# AdaptiveLightingHub.net
KiCad netlist of a schematic drawn in Altium Designer
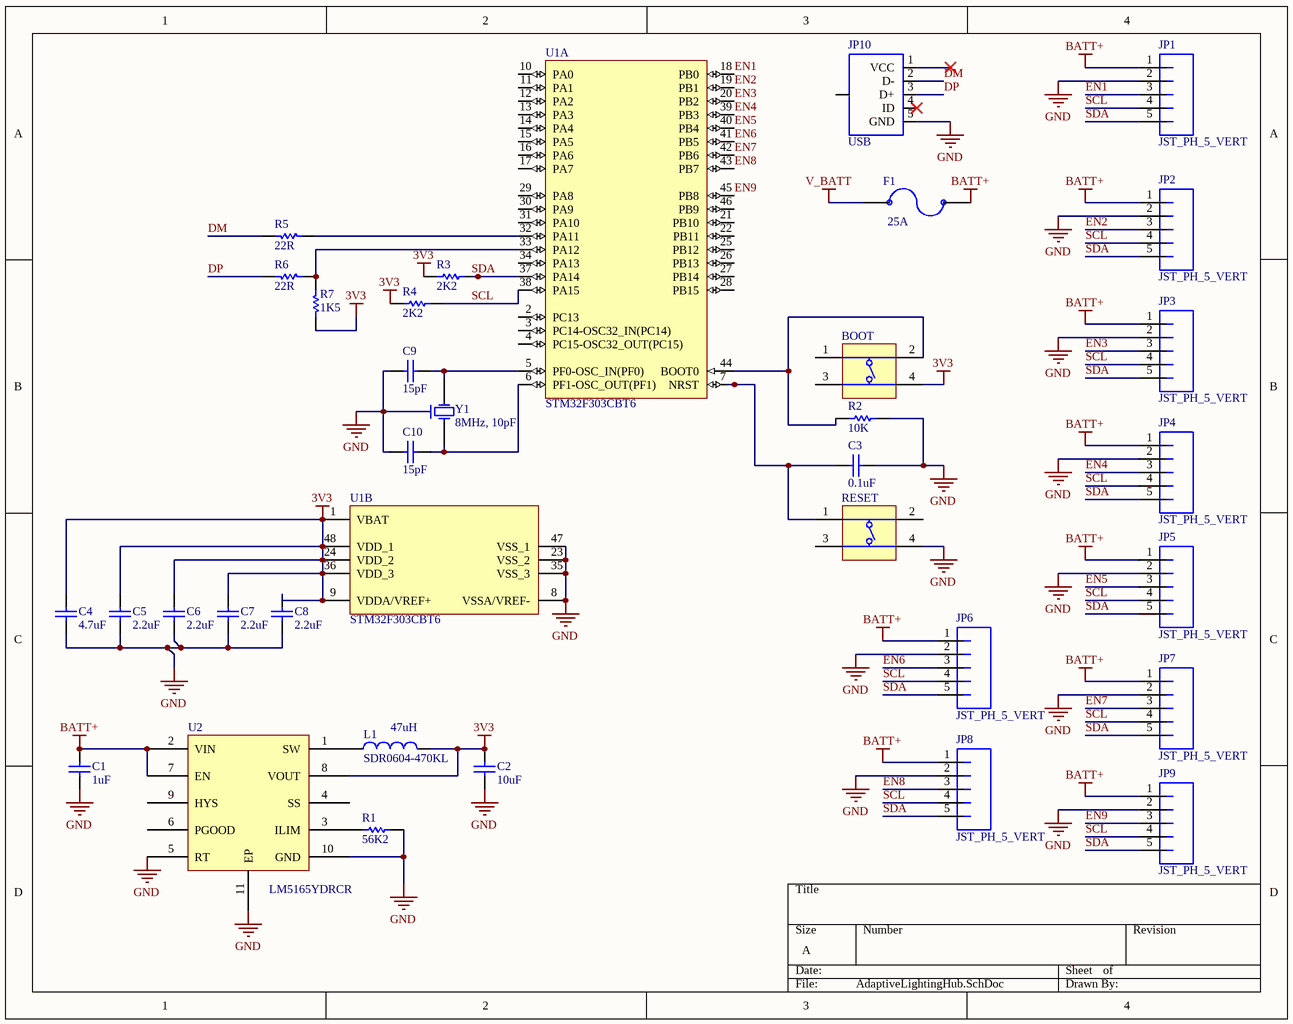
[diagram p0: AdaptiveLightingHub.SchDoc]

(export (version "E")
  (design (tool "Eeschema 10.0.6"))
  (components
    (comp (ref "BOOT")
      (value "~")
      (footprint "SWITCH")
      (description "Switch, SPNO Push Button SMD")
      (fields
        (field (name "MANUFACTURER") "C&K Components")
        (field (name "PARTNUMBER") "PTS810 SJM 250 SMTR LFS")
      )
      (libsource (lib "Components") (part "DIPT-DTSM-6"))
    )
    (comp (ref "C1")
      (value "1uF")
      (footprint "C0805[2012X120]")
      (description "CAP_1uF 100V 20% 0805 (2012 metric)")
      (fields (field (name "MANUFACTURER") "TDK") (field (name "PARTNUMBER") "C2012X7S2A474M125AE"))
      (libsource (lib "Capacitors") (part "CAP_1uF_100V_0805_20%"))
    )
    (comp (ref "C2")
      (value "10uF")
      (footprint "C0402[1005X55]")
      (description "10uF 6.3V 20% 0402 (1005 Metric)")
      (fields (field (name "PARTNUMBER") "GRM155R60J106ME44D") (field (name "MANUFACTURER") "Murata"))
      (libsource (lib "Capacitors") (part "CAP_10uF_6.3V_0402_20%"))
    )
    (comp (ref "C3")
      (value "0.1uF")
      (footprint "C0402[1005X55]")
      (description "0.1uF 6.3V 10% 0402 (1005 Metric)")
      (fields (field (name "TOLERANCE") "10%") (field (name "PARTNUMBER") "GRM155R70J104KA01D"))
      (libsource (lib "Capacitors") (part "CAP_0.1uF_6.3V_0402_10%"))
    )
    (comp (ref "C4")
      (value "4.7uF")
      (footprint "C0402[1005X55]")
      (description "4.7uF 6.3V 20% 0402 (1005 Metric)")
      (fields (field (name "TOLERANCE") "20%") (field (name "PARTNUMBER") "GRM155R60J475ME47D"))
      (libsource (lib "Capacitors") (part "CAP_4.7uF_6.3V_0402_20%"))
    )
    (comp (ref "C5")
      (value "2.2uF")
      (footprint "C0402[1005X55]")
      (description "2.2uF 6.3V 20% 0402 (1005 Metric)")
      (fields (field (name "TOLERANCE") "20%") (field (name "PARTNUMBER") "GRM155R60J225ME15D"))
      (libsource (lib "Capacitors") (part "CAP_2.2uF_6.3V_0402_20%"))
    )
    (comp (ref "C6")
      (value "2.2uF")
      (footprint "C0402[1005X55]")
      (description "2.2uF 6.3V 20% 0402 (1005 Metric)")
      (fields (field (name "TOLERANCE") "20%") (field (name "PARTNUMBER") "GRM155R60J225ME15D"))
      (libsource (lib "Capacitors") (part "CAP_2.2uF_6.3V_0402_20%"))
    )
    (comp (ref "C7")
      (value "2.2uF")
      (footprint "C0402[1005X55]")
      (description "2.2uF 6.3V 20% 0402 (1005 Metric)")
      (fields (field (name "TOLERANCE") "20%") (field (name "PARTNUMBER") "GRM155R60J225ME15D"))
      (libsource (lib "Capacitors") (part "CAP_2.2uF_6.3V_0402_20%"))
    )
    (comp (ref "C8")
      (value "2.2uF")
      (footprint "C0402[1005X55]")
      (description "2.2uF 6.3V 20% 0402 (1005 Metric)")
      (fields (field (name "TOLERANCE") "20%") (field (name "PARTNUMBER") "GRM155R60J225ME15D"))
      (libsource (lib "Capacitors") (part "CAP_2.2uF_6.3V_0402_20%"))
    )
    (comp (ref "C9")
      (value "15pF")
      (footprint "C0402[1005X55]")
      (description "15pF 50V 5% 0402 (1005 Metric)")
      (fields (field (name "TOLERANCE") "5%") (field (name "PARTNUMBER") "GRM1555C1H150JA01D"))
      (libsource (lib "Capacitors") (part "CAP_15pF_50V_0402_5%"))
    )
    (comp (ref "C10")
      (value "15pF")
      (footprint "C0402[1005X55]")
      (description "15pF 50V 5% 0402 (1005 Metric)")
      (fields (field (name "TOLERANCE") "5%") (field (name "PARTNUMBER") "GRM1555C1H150JA01D"))
      (libsource (lib "Capacitors") (part "CAP_15pF_50V_0402_5%"))
    )
    (comp (ref "F1")
      (value "FUSE 1206")
      (footprint "1206_FUSE")
      (description "Surface Mount Fuses UST 1206 FUSE 25A F")
      (fields
        (field (name "PARTNUMBER") "3413.0332.22")
        (field (name "MANUFACTURER") "Schurter")
        (field (name "CURRENT") "25A")
      )
      (libsource (lib "Components") (part "FUSE 1206"))
    )
    (comp (ref "JP1")
      (value "JST_PH_5_VERT")
      (footprint "JST-PH-5-PTH-VERT")
      (fields
        (field (name "MANUFACTURER") "JST Sales America, Inc.")
        (field (name "PARTNUMBER") "B5B-PH-K-S(LF)(SN)")
      )
      (libsource (lib "Connectors") (part "JST_PH_5_VERT"))
    )
    (comp (ref "JP2")
      (value "JST_PH_5_VERT")
      (footprint "JST-PH-5-PTH-VERT")
      (fields
        (field (name "MANUFACTURER") "JST Sales America, Inc.")
        (field (name "PARTNUMBER") "B5B-PH-K-S(LF)(SN)")
      )
      (libsource (lib "Connectors") (part "JST_PH_5_VERT"))
    )
    (comp (ref "JP3")
      (value "JST_PH_5_VERT")
      (footprint "JST-PH-5-PTH-VERT")
      (fields
        (field (name "MANUFACTURER") "JST Sales America, Inc.")
        (field (name "PARTNUMBER") "B5B-PH-K-S(LF)(SN)")
      )
      (libsource (lib "Connectors") (part "JST_PH_5_VERT"))
    )
    (comp (ref "JP4")
      (value "JST_PH_5_VERT")
      (footprint "JST-PH-5-PTH-VERT")
      (fields
        (field (name "MANUFACTURER") "JST Sales America, Inc.")
        (field (name "PARTNUMBER") "B5B-PH-K-S(LF)(SN)")
      )
      (libsource (lib "Connectors") (part "JST_PH_5_VERT"))
    )
    (comp (ref "JP5")
      (value "JST_PH_5_VERT")
      (footprint "JST-PH-5-PTH-VERT")
      (fields
        (field (name "MANUFACTURER") "JST Sales America, Inc.")
        (field (name "PARTNUMBER") "B5B-PH-K-S(LF)(SN)")
      )
      (libsource (lib "Connectors") (part "JST_PH_5_VERT"))
    )
    (comp (ref "JP6")
      (value "JST_PH_5_VERT")
      (footprint "JST-PH-5-PTH-VERT")
      (fields
        (field (name "MANUFACTURER") "JST Sales America, Inc.")
        (field (name "PARTNUMBER") "B5B-PH-K-S(LF)(SN)")
      )
      (libsource (lib "Connectors") (part "JST_PH_5_VERT"))
    )
    (comp (ref "JP7")
      (value "JST_PH_5_VERT")
      (footprint "JST-PH-5-PTH-VERT")
      (fields
        (field (name "MANUFACTURER") "JST Sales America, Inc.")
        (field (name "PARTNUMBER") "B5B-PH-K-S(LF)(SN)")
      )
      (libsource (lib "Connectors") (part "JST_PH_5_VERT"))
    )
    (comp (ref "JP8")
      (value "JST_PH_5_VERT")
      (footprint "JST-PH-5-PTH-VERT")
      (fields
        (field (name "MANUFACTURER") "JST Sales America, Inc.")
        (field (name "PARTNUMBER") "B5B-PH-K-S(LF)(SN)")
      )
      (libsource (lib "Connectors") (part "JST_PH_5_VERT"))
    )
    (comp (ref "JP9")
      (value "JST_PH_5_VERT")
      (footprint "JST-PH-5-PTH-VERT")
      (fields
        (field (name "MANUFACTURER") "JST Sales America, Inc.")
        (field (name "PARTNUMBER") "B5B-PH-K-S(LF)(SN)")
      )
      (libsource (lib "Connectors") (part "JST_PH_5_VERT"))
    )
    (comp (ref "JP10")
      (value "USB")
      (footprint "USB-MICROB")
      (fields (field (name "PARTNUMBER") "10118192-0001LF") (field (name "MANUFACTURER") "Amphenol FCI"))
      (libsource (lib "Connectors") (part "USB_MICROB_SMT"))
    )
    (comp (ref "L1")
      (value "SDR0604-470KL")
      (footprint "SDR0604")
      (description "47uH 10% 0.72A 0604")
      (fields (field (name "MANUFACTURER") "Bourns") (field (name "ALTIUM_VALUE") "47uH"))
      (libsource (lib "Inductors") (part "SDR0604-470KL"))
    )
    (comp (ref "R1")
      (value "56K2")
      (footprint "R0402[1005]")
      (description "56K2 0.063W 1% 0402 (1005 Metric)")
      (fields (field (name "MANUFACTURER") "KOA Speer") (field (name "PARTNUMBER") "RK73H1ETTP5622F"))
      (libsource (lib "Resistors") (part "RES_56K2_0402_1%"))
    )
    (comp (ref "R2")
      (value "10K")
      (footprint "R0402[1005]")
      (description "10K 0.063W 1% 0402 (1005 Metric)")
      (fields (field (name "TOLERANCE") "1%") (field (name "POWER") "0.063W"))
      (libsource (lib "Resistors") (part "RES_10K_0402_1%"))
    )
    (comp (ref "R3")
      (value "2K2")
      (footprint "R0402[1005]")
      (description "2K2 0.063W 1% 0402 (1005 Metric)")
      (fields (field (name "MANUFACTURER") "KOA Speer") (field (name "PARTNUMBER") "RK73H1ETTP2201F"))
      (libsource (lib "Resistors") (part "RES_2K2_0402_1%"))
    )
    (comp (ref "R4")
      (value "2K2")
      (footprint "R0402[1005]")
      (description "2K2 0.063W 1% 0402 (1005 Metric)")
      (fields (field (name "MANUFACTURER") "KOA Speer") (field (name "PARTNUMBER") "RK73H1ETTP2201F"))
      (libsource (lib "Resistors") (part "RES_2K2_0402_1%"))
    )
    (comp (ref "R5")
      (value "22R")
      (footprint "R0402[1005]")
      (description "22R 0.063W 1% 0402 (1005 Metric)")
      (fields (field (name "POWER") "0.063W") (field (name "TOLERANCE") "1%"))
      (libsource (lib "Resistors") (part "RES_22R_0402_1%"))
    )
    (comp (ref "R6")
      (value "22R")
      (footprint "R0402[1005]")
      (description "22R 0.063W 1% 0402 (1005 Metric)")
      (fields (field (name "POWER") "0.063W") (field (name "TOLERANCE") "1%"))
      (libsource (lib "Resistors") (part "RES_22R_0402_1%"))
    )
    (comp (ref "R7")
      (value "1K5")
      (footprint "R0402[1005]")
      (description "1K5 0.063W 1% 0402 (1005 Metric)")
      (fields (field (name "MANUFACTURER") "KOA Speer") (field (name "PARTNUMBER") "RK73H1ETTP1501F"))
      (libsource (lib "Resistors") (part "RES_1K5_0402_1%"))
    )
    (comp (ref "RESET")
      (value "~")
      (footprint "SWITCH")
      (description "Switch, SPNO Push Button SMD")
      (fields
        (field (name "MANUFACTURER") "C&K Components")
        (field (name "PARTNUMBER") "PTS810 SJM 250 SMTR LFS")
      )
      (libsource (lib "Components") (part "DIPT-DTSM-6"))
    )
    (comp (ref "U1")
      (value "STM32F303CBT6")
      (footprint "LQFP-48")
      (fields (field (name "MANUFACTURER") "STMicroelectronics"))
      (libsource (lib "ICs") (part "STM32F303CBT6"))
    )
    (comp (ref "U2")
      (value "LM5165YDRCR")
      (footprint "VSON-10 (3mmx3mm)")
      (description "LM5165 3-V to 65-V Input, 150-mA Synchronous Buck Converter")
      (fields (field (name "MANUFACTURER") "Texas Instruments"))
      (libsource (lib "ICs") (part "LM5165YDRCR"))
    )
    (comp (ref "Y1")
      (value "8MHz, 10pF")
      (footprint "ABRA-ABM3B-4_V")
      (fields (field (name "PARTNUMBER") "ABM3B-8.000MHZ-10-1UT") (field (name "MANUFACTURER") "ABRACON"))
      (libsource (lib "Components") (part "ABRA-ABM3B-4"))
    )
  )
  (nets
    (net (code "1") (name "/DM") (class "Default")
      (node (ref "JP10") (pin "2") (pinfunction "D-_2") (pintype "passive"))
      (node (ref "R5") (pin "2") (pinfunction "2_2") (pintype "passive"))
    )
    (net (code "2") (name "/DP") (class "Default")
      (node (ref "JP10") (pin "3") (pinfunction "D+_3") (pintype "passive"))
      (node (ref "R6") (pin "2") (pinfunction "2_2") (pintype "passive"))
    )
    (net (code "3") (name "/EN1") (class "Default")
      (node (ref "JP1") (pin "3") (pinfunction "3_3") (pintype "passive"))
      (node (ref "U1") (pin "18") (pinfunction "PB0_18") (pintype "bidirectional"))
    )
    (net (code "4") (name "/EN2") (class "Default")
      (node (ref "JP2") (pin "3") (pinfunction "3_3") (pintype "passive"))
      (node (ref "U1") (pin "19") (pinfunction "PB1_19") (pintype "bidirectional"))
    )
    (net (code "5") (name "/EN3") (class "Default")
      (node (ref "JP3") (pin "3") (pinfunction "3_3") (pintype "passive"))
      (node (ref "U1") (pin "20") (pinfunction "PB2_20") (pintype "bidirectional"))
    )
    (net (code "6") (name "/EN4") (class "Default")
      (node (ref "JP4") (pin "3") (pinfunction "3_3") (pintype "passive"))
      (node (ref "U1") (pin "39") (pinfunction "PB3_39") (pintype "bidirectional"))
    )
    (net (code "7") (name "/EN5") (class "Default")
      (node (ref "JP5") (pin "3") (pinfunction "3_3") (pintype "passive"))
      (node (ref "U1") (pin "40") (pinfunction "PB4_40") (pintype "bidirectional"))
    )
    (net (code "8") (name "/EN6") (class "Default")
      (node (ref "JP6") (pin "3") (pinfunction "3_3") (pintype "passive"))
      (node (ref "U1") (pin "41") (pinfunction "PB5_41") (pintype "bidirectional"))
    )
    (net (code "9") (name "/EN7") (class "Default")
      (node (ref "JP7") (pin "3") (pinfunction "3_3") (pintype "passive"))
      (node (ref "U1") (pin "42") (pinfunction "PB6_42") (pintype "bidirectional"))
    )
    (net (code "10") (name "/EN8") (class "Default")
      (node (ref "JP8") (pin "3") (pinfunction "3_3") (pintype "passive"))
      (node (ref "U1") (pin "43") (pinfunction "PB7_43") (pintype "bidirectional"))
    )
    (net (code "11") (name "/EN9") (class "Default")
      (node (ref "JP9") (pin "3") (pinfunction "3_3") (pintype "passive"))
      (node (ref "U1") (pin "45") (pinfunction "PB8_45") (pintype "bidirectional"))
    )
    (net (code "12") (name "/SCL") (class "Default")
      (node (ref "JP1") (pin "4") (pinfunction "4_4") (pintype "passive"))
      (node (ref "JP2") (pin "4") (pinfunction "4_4") (pintype "passive"))
      (node (ref "JP3") (pin "4") (pinfunction "4_4") (pintype "passive"))
      (node (ref "JP4") (pin "4") (pinfunction "4_4") (pintype "passive"))
      (node (ref "JP5") (pin "4") (pinfunction "4_4") (pintype "passive"))
      (node (ref "JP6") (pin "4") (pinfunction "4_4") (pintype "passive"))
      (node (ref "JP7") (pin "4") (pinfunction "4_4") (pintype "passive"))
      (node (ref "JP8") (pin "4") (pinfunction "4_4") (pintype "passive"))
      (node (ref "JP9") (pin "4") (pinfunction "4_4") (pintype "passive"))
      (node (ref "R4") (pin "2") (pinfunction "2_2") (pintype "passive"))
      (node (ref "U1") (pin "38") (pinfunction "PA15_38") (pintype "bidirectional"))
    )
    (net (code "13") (name "/SDA") (class "Default")
      (node (ref "JP1") (pin "5") (pinfunction "5_5") (pintype "passive"))
      (node (ref "JP2") (pin "5") (pinfunction "5_5") (pintype "passive"))
      (node (ref "JP3") (pin "5") (pinfunction "5_5") (pintype "passive"))
      (node (ref "JP4") (pin "5") (pinfunction "5_5") (pintype "passive"))
      (node (ref "JP5") (pin "5") (pinfunction "5_5") (pintype "passive"))
      (node (ref "JP6") (pin "5") (pinfunction "5_5") (pintype "passive"))
      (node (ref "JP7") (pin "5") (pinfunction "5_5") (pintype "passive"))
      (node (ref "JP8") (pin "5") (pinfunction "5_5") (pintype "passive"))
      (node (ref "JP9") (pin "5") (pinfunction "5_5") (pintype "passive"))
      (node (ref "R3") (pin "2") (pinfunction "2_2") (pintype "passive"))
      (node (ref "U1") (pin "37") (pinfunction "PA14_37") (pintype "bidirectional"))
    )
    (net (code "14") (name "3V3") (class "Default")
      (node (ref "BOOT") (pin "4") (pinfunction "T3_4") (pintype "passive"))
      (node (ref "C2") (pin "2") (pinfunction "2_2") (pintype "passive"))
      (node (ref "C4") (pin "2") (pinfunction "2_2") (pintype "passive"))
      (node (ref "C5") (pin "2") (pinfunction "2_2") (pintype "passive"))
      (node (ref "C6") (pin "2") (pinfunction "2_2") (pintype "passive"))
      (node (ref "C7") (pin "2") (pinfunction "2_2") (pintype "passive"))
      (node (ref "C8") (pin "2") (pinfunction "2_2") (pintype "passive"))
      (node (ref "L1") (pin "2") (pinfunction "2_2") (pintype "passive"))
      (node (ref "R3") (pin "1") (pinfunction "1_1") (pintype "passive"))
      (node (ref "R4") (pin "1") (pinfunction "1_1") (pintype "passive"))
      (node (ref "R7") (pin "1") (pinfunction "1_1") (pintype "passive"))
      (node (ref "U1") (pin "1") (pinfunction "VBAT_1") (pintype "power_in"))
      (node (ref "U1") (pin "24") (pinfunction "VDD_2_24") (pintype "power_in"))
      (node (ref "U1") (pin "36") (pinfunction "VDD_3_36") (pintype "power_in"))
      (node (ref "U1") (pin "48") (pinfunction "VDD_1_48") (pintype "power_in"))
      (node (ref "U1") (pin "9") (pinfunction "VDDA/VREF+_9") (pintype "power_in"))
      (node (ref "U2") (pin "8") (pinfunction "VOUT_8") (pintype "passive"))
    )
    (net (code "15") (name "BATT+") (class "Default")
      (node (ref "C1") (pin "2") (pinfunction "2_2") (pintype "passive"))
      (node (ref "F1") (pin "2") (pinfunction "2_2") (pintype "passive"))
      (node (ref "JP1") (pin "1") (pinfunction "1_1") (pintype "passive"))
      (node (ref "JP2") (pin "1") (pinfunction "1_1") (pintype "passive"))
      (node (ref "JP3") (pin "1") (pinfunction "1_1") (pintype "passive"))
      (node (ref "JP4") (pin "1") (pinfunction "1_1") (pintype "passive"))
      (node (ref "JP5") (pin "1") (pinfunction "1_1") (pintype "passive"))
      (node (ref "JP6") (pin "1") (pinfunction "1_1") (pintype "passive"))
      (node (ref "JP7") (pin "1") (pinfunction "1_1") (pintype "passive"))
      (node (ref "JP8") (pin "1") (pinfunction "1_1") (pintype "passive"))
      (node (ref "JP9") (pin "1") (pinfunction "1_1") (pintype "passive"))
      (node (ref "U2") (pin "2") (pinfunction "VIN_2") (pintype "passive"))
      (node (ref "U2") (pin "7") (pinfunction "EN_7") (pintype "passive"))
    )
    (net (code "16") (name "GND") (class "Default")
      (node (ref "C1") (pin "1") (pinfunction "1_1") (pintype "passive"))
      (node (ref "C10") (pin "1") (pinfunction "1_1") (pintype "passive"))
      (node (ref "C2") (pin "1") (pinfunction "1_1") (pintype "passive"))
      (node (ref "C3") (pin "2") (pinfunction "2_2") (pintype "passive"))
      (node (ref "C4") (pin "1") (pinfunction "1_1") (pintype "passive"))
      (node (ref "C5") (pin "1") (pinfunction "1_1") (pintype "passive"))
      (node (ref "C6") (pin "1") (pinfunction "1_1") (pintype "passive"))
      (node (ref "C7") (pin "1") (pinfunction "1_1") (pintype "passive"))
      (node (ref "C8") (pin "1") (pinfunction "1_1") (pintype "passive"))
      (node (ref "C9") (pin "1") (pinfunction "1_1") (pintype "passive"))
      (node (ref "JP1") (pin "2") (pinfunction "2_2") (pintype "passive"))
      (node (ref "JP10") (pin "5") (pinfunction "GND_5") (pintype "passive"))
      (node (ref "JP2") (pin "2") (pinfunction "2_2") (pintype "passive"))
      (node (ref "JP3") (pin "2") (pinfunction "2_2") (pintype "passive"))
      (node (ref "JP4") (pin "2") (pinfunction "2_2") (pintype "passive"))
      (node (ref "JP5") (pin "2") (pinfunction "2_2") (pintype "passive"))
      (node (ref "JP6") (pin "2") (pinfunction "2_2") (pintype "passive"))
      (node (ref "JP7") (pin "2") (pinfunction "2_2") (pintype "passive"))
      (node (ref "JP8") (pin "2") (pinfunction "2_2") (pintype "passive"))
      (node (ref "JP9") (pin "2") (pinfunction "2_2") (pintype "passive"))
      (node (ref "R1") (pin "2") (pinfunction "2_2") (pintype "passive"))
      (node (ref "R2") (pin "2") (pinfunction "2_2") (pintype "passive"))
      (node (ref "RESET") (pin "4") (pinfunction "T3_4") (pintype "passive"))
      (node (ref "U1") (pin "23") (pinfunction "VSS_2_23") (pintype "power_in"))
      (node (ref "U1") (pin "35") (pinfunction "VSS_3_35") (pintype "power_in"))
      (node (ref "U1") (pin "47") (pinfunction "VSS_1_47") (pintype "power_in"))
      (node (ref "U1") (pin "8") (pinfunction "VSSA/VREF-_8") (pintype "power_in"))
      (node (ref "U2") (pin "10") (pinfunction "GND_10") (pintype "passive"))
      (node (ref "U2") (pin "11") (pinfunction "EP_11") (pintype "passive"))
      (node (ref "U2") (pin "5") (pinfunction "RT_5") (pintype "passive"))
      (node (ref "Y1") (pin "2") (pinfunction "2_2") (pintype "passive"))
    )
    (net (code "17") (name "Net-(BOOT-T2)") (class "Default")
      (node (ref "BOOT") (pin "2") (pinfunction "T2_2") (pintype "passive"))
      (node (ref "R2") (pin "1") (pinfunction "1_1") (pintype "passive"))
      (node (ref "U1") (pin "44") (pinfunction "BOOT0_44") (pintype "input"))
    )
    (net (code "18") (name "Net-(RESET-T1)") (class "Default")
      (node (ref "C3") (pin "1") (pinfunction "1_1") (pintype "passive"))
      (node (ref "RESET") (pin "1") (pinfunction "T1_1") (pintype "passive"))
      (node (ref "U1") (pin "7") (pinfunction "NRST_7") (pintype "bidirectional"))
    )
    (net (code "19") (name "Net-(U1A-PA11)") (class "Default")
      (node (ref "R5") (pin "1") (pinfunction "1_1") (pintype "passive"))
      (node (ref "U1") (pin "32") (pinfunction "PA11_32") (pintype "bidirectional"))
    )
    (net (code "20") (name "Net-(U1A-PA12)") (class "Default")
      (node (ref "R6") (pin "1") (pinfunction "1_1") (pintype "passive"))
      (node (ref "R7") (pin "2") (pinfunction "2_2") (pintype "passive"))
      (node (ref "U1") (pin "33") (pinfunction "PA12_33") (pintype "bidirectional"))
    )
    (net (code "21") (name "Net-(U1A-PF0-OSC_IN(PF0))") (class "Default")
      (node (ref "C9") (pin "2") (pinfunction "2_2") (pintype "passive"))
      (node (ref "U1") (pin "5") (pinfunction "PF0-OSC_IN(PF0)_5") (pintype "bidirectional"))
      (node (ref "Y1") (pin "1") (pinfunction "X1_1") (pintype "passive"))
    )
    (net (code "22") (name "Net-(U1A-PF1-OSC_OUT(PF1))") (class "Default")
      (node (ref "C10") (pin "2") (pinfunction "2_2") (pintype "passive"))
      (node (ref "U1") (pin "6") (pinfunction "PF1-OSC_OUT(PF1)_6") (pintype "bidirectional"))
      (node (ref "Y1") (pin "3") (pinfunction "X2_3") (pintype "passive"))
    )
    (net (code "23") (name "Net-(U2-ILIM)") (class "Default")
      (node (ref "R1") (pin "1") (pinfunction "1_1") (pintype "passive"))
      (node (ref "U2") (pin "3") (pinfunction "ILIM_3") (pintype "passive"))
    )
    (net (code "24") (name "Net-(U2-SW)") (class "Default")
      (node (ref "L1") (pin "1") (pinfunction "1_1") (pintype "passive"))
      (node (ref "U2") (pin "1") (pinfunction "SW_1") (pintype "passive"))
    )
    (net (code "25") (name "V_BATT") (class "Default")
      (node (ref "F1") (pin "1") (pinfunction "1_1") (pintype "passive"))
    )
    (net (code "26") (name "unconnected-(BOOT-T1-Pad1)") (class "Default")
      (node (ref "BOOT") (pin "1") (pinfunction "T1_1") (pintype "passive"))
    )
    (net (code "27") (name "unconnected-(BOOT-T3-Pad3)") (class "Default")
      (node (ref "BOOT") (pin "3") (pinfunction "T3_3") (pintype "passive"))
    )
    (net (code "28") (name "unconnected-(JP10-ID-Pad4)") (class "Default")
      (node (ref "JP10") (pin "4") (pinfunction "ID_4") (pintype "passive+no_connect"))
    )
    (net (code "29") (name "unconnected-(JP10-SHIELD-Pad6)") (class "Default")
      (node (ref "JP10") (pin "6") (pinfunction "SHIELD_6") (pintype "passive"))
    )
    (net (code "30") (name "unconnected-(JP10-VCC-Pad1)") (class "Default")
      (node (ref "JP10") (pin "1") (pinfunction "VCC_1") (pintype "passive+no_connect"))
    )
    (net (code "31") (name "unconnected-(RESET-T2-Pad2)") (class "Default")
      (node (ref "RESET") (pin "2") (pinfunction "T2_2") (pintype "passive"))
    )
    (net (code "32") (name "unconnected-(RESET-T3-Pad3)") (class "Default")
      (node (ref "RESET") (pin "3") (pinfunction "T3_3") (pintype "passive"))
    )
    (net (code "33") (name "unconnected-(U1A-PA0-Pad10)") (class "Default")
      (node (ref "U1") (pin "10") (pinfunction "PA0_10") (pintype "bidirectional"))
    )
    (net (code "34") (name "unconnected-(U1A-PA1-Pad11)") (class "Default")
      (node (ref "U1") (pin "11") (pinfunction "PA1_11") (pintype "bidirectional"))
    )
    (net (code "35") (name "unconnected-(U1A-PA2-Pad12)") (class "Default")
      (node (ref "U1") (pin "12") (pinfunction "PA2_12") (pintype "bidirectional"))
    )
    (net (code "36") (name "unconnected-(U1A-PA3-Pad13)") (class "Default")
      (node (ref "U1") (pin "13") (pinfunction "PA3_13") (pintype "bidirectional"))
    )
    (net (code "37") (name "unconnected-(U1A-PA4-Pad14)") (class "Default")
      (node (ref "U1") (pin "14") (pinfunction "PA4_14") (pintype "bidirectional"))
    )
    (net (code "38") (name "unconnected-(U1A-PA5-Pad15)") (class "Default")
      (node (ref "U1") (pin "15") (pinfunction "PA5_15") (pintype "bidirectional"))
    )
    (net (code "39") (name "unconnected-(U1A-PA6-Pad16)") (class "Default")
      (node (ref "U1") (pin "16") (pinfunction "PA6_16") (pintype "bidirectional"))
    )
    (net (code "40") (name "unconnected-(U1A-PA7-Pad17)") (class "Default")
      (node (ref "U1") (pin "17") (pinfunction "PA7_17") (pintype "bidirectional"))
    )
    (net (code "41") (name "unconnected-(U1A-PA8-Pad29)") (class "Default")
      (node (ref "U1") (pin "29") (pinfunction "PA8_29") (pintype "bidirectional"))
    )
    (net (code "42") (name "unconnected-(U1A-PA9-Pad30)") (class "Default")
      (node (ref "U1") (pin "30") (pinfunction "PA9_30") (pintype "bidirectional"))
    )
    (net (code "43") (name "unconnected-(U1A-PA10-Pad31)") (class "Default")
      (node (ref "U1") (pin "31") (pinfunction "PA10_31") (pintype "bidirectional"))
    )
    (net (code "44") (name "unconnected-(U1A-PA13-Pad34)") (class "Default")
      (node (ref "U1") (pin "34") (pinfunction "PA13_34") (pintype "bidirectional"))
    )
    (net (code "45") (name "unconnected-(U1A-PB9-Pad46)") (class "Default")
      (node (ref "U1") (pin "46") (pinfunction "PB9_46") (pintype "bidirectional"))
    )
    (net (code "46") (name "unconnected-(U1A-PB10-Pad21)") (class "Default")
      (node (ref "U1") (pin "21") (pinfunction "PB10_21") (pintype "bidirectional"))
    )
    (net (code "47") (name "unconnected-(U1A-PB11-Pad22)") (class "Default")
      (node (ref "U1") (pin "22") (pinfunction "PB11_22") (pintype "bidirectional"))
    )
    (net (code "48") (name "unconnected-(U1A-PB12-Pad25)") (class "Default")
      (node (ref "U1") (pin "25") (pinfunction "PB12_25") (pintype "bidirectional"))
    )
    (net (code "49") (name "unconnected-(U1A-PB13-Pad26)") (class "Default")
      (node (ref "U1") (pin "26") (pinfunction "PB13_26") (pintype "bidirectional"))
    )
    (net (code "50") (name "unconnected-(U1A-PB14-Pad27)") (class "Default")
      (node (ref "U1") (pin "27") (pinfunction "PB14_27") (pintype "bidirectional"))
    )
    (net (code "51") (name "unconnected-(U1A-PB15-Pad28)") (class "Default")
      (node (ref "U1") (pin "28") (pinfunction "PB15_28") (pintype "bidirectional"))
    )
    (net (code "52") (name "unconnected-(U1A-PC13-Pad2)") (class "Default")
      (node (ref "U1") (pin "2") (pinfunction "PC13_2") (pintype "bidirectional"))
    )
    (net (code "53") (name "unconnected-(U1A-PC14-OSC32_IN(PC14)-Pad3)") (class "Default")
      (node (ref "U1") (pin "3") (pinfunction "PC14-OSC32_IN(PC14)_3") (pintype "bidirectional"))
    )
    (net (code "54") (name "unconnected-(U1A-PC15-OSC32_OUT(PC15)-Pad4)") (class "Default")
      (node (ref "U1") (pin "4") (pinfunction "PC15-OSC32_OUT(PC15)_4") (pintype "bidirectional"))
    )
    (net (code "55") (name "unconnected-(U2-HYS-Pad9)") (class "Default")
      (node (ref "U2") (pin "9") (pinfunction "HYS_9") (pintype "passive"))
    )
    (net (code "56") (name "unconnected-(U2-PGOOD-Pad6)") (class "Default")
      (node (ref "U2") (pin "6") (pinfunction "PGOOD_6") (pintype "passive"))
    )
    (net (code "57") (name "unconnected-(U2-SS-Pad4)") (class "Default")
      (node (ref "U2") (pin "4") (pinfunction "SS_4") (pintype "passive"))
    )
  )
)
